# MA18V17.net
KiCad netlist of a schematic drawn in Altium Designer
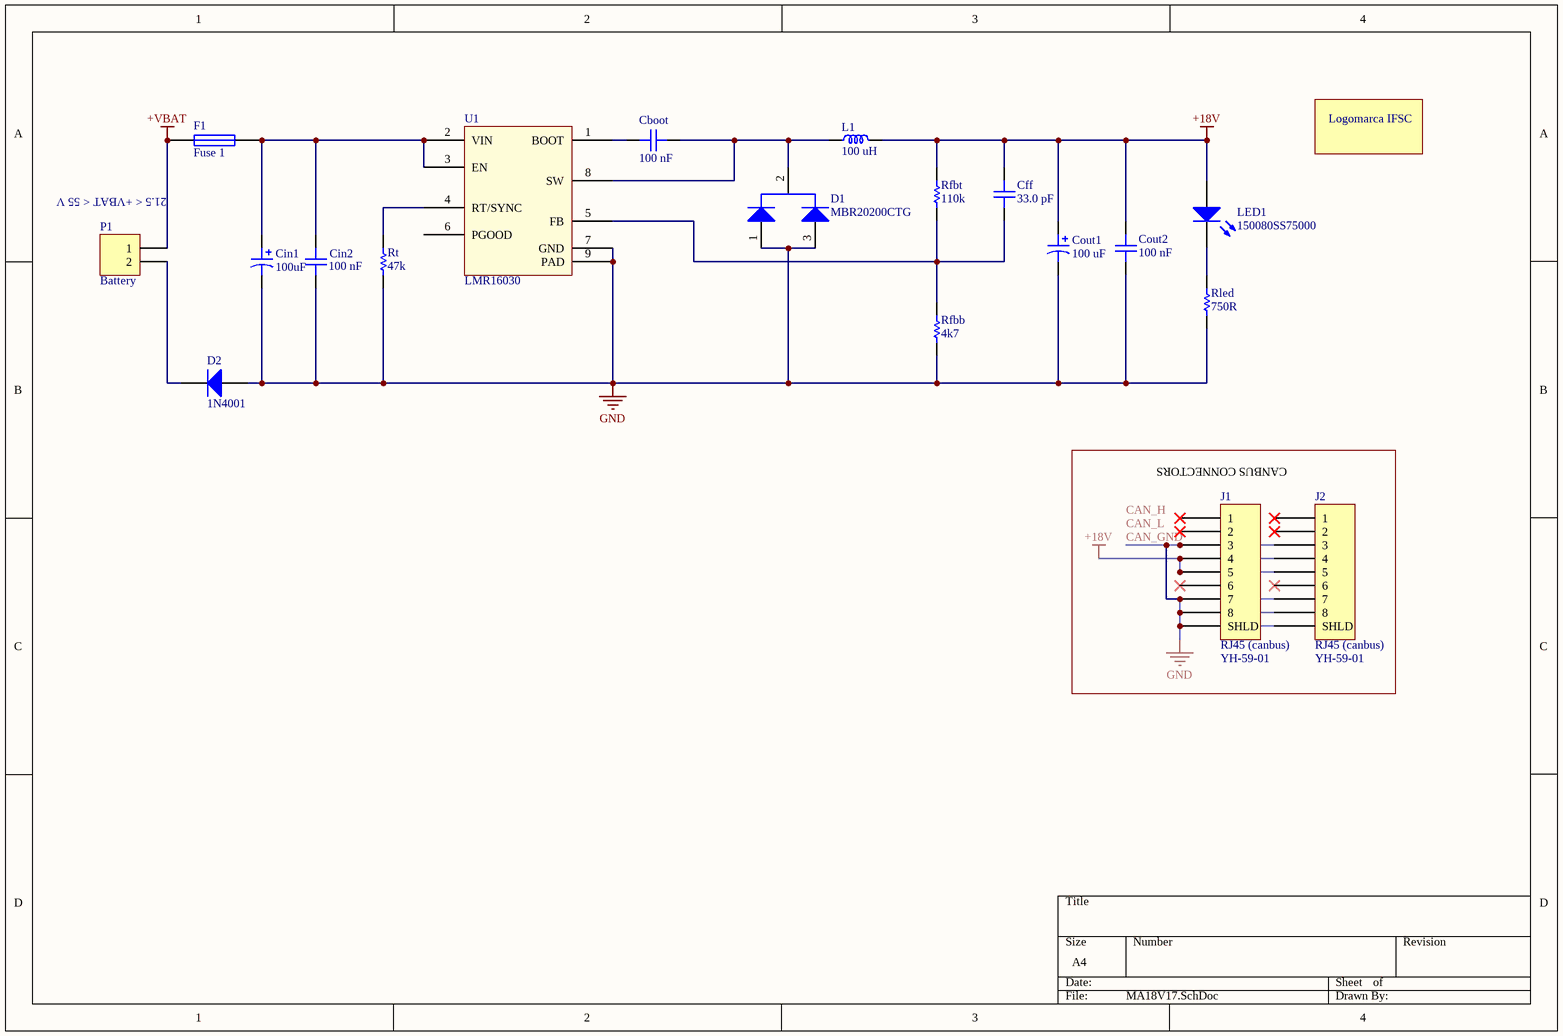
[diagram p0: MA18V17.SchDoc]

(export (version "E")
  (design (tool "Eeschema 10.0.6"))
  (components
    (comp (ref "Cboot")
      (value "100 nF")
      (footprint "0805C")
      (description "Capacitor")
      (fields (field (name "VOLTAGE") "25 V") (field (name "PUBLISHER") "Altium Limited"))
      (libsource (lib "passive") (part "Capacitor"))
    )
    (comp (ref "Cff")
      (value "33.0 pF")
      (footprint "0805C")
      (description "Capacitor")
      (fields (field (name "VOLTAGE") "16 V") (field (name "PUBLISHER") "Altium Limited"))
      (libsource (lib "passive") (part "Capacitor"))
    )
    (comp (ref "Cin1")
      (value "100uF")
      (footprint "CP-RAD-12.5mm-35.0mm-5.0mm")
      (description "Solid Aluminum Capacitor with Organic Semiconductor Electrolyte: 100uF, 10V, Bulk Pack")
      (fields (field (name "VOLTAGE") "100V") (field (name "PUBLISHER") "Altium Limited"))
      (libsource (lib "passive") (part "CapacitorPol"))
    )
    (comp (ref "Cin2")
      (value "100 nF")
      (footprint "0805C")
      (description "Capacitor")
      (fields (field (name "VOLTAGE") "100 V") (field (name "PUBLISHER") "Altium Limited"))
      (libsource (lib "passive") (part "Capacitor"))
    )
    (comp (ref "Cout1")
      (value "100 uF")
      (footprint "CP-RAD-12.5mm-35.0mm-5.0mm")
      (description "Solid Aluminum Capacitor with Organic Semiconductor Electrolyte: 100uF, 10V, Bulk Pack")
      (fields (field (name "VOLTAGE") "25 V") (field (name "PUBLISHER") "Altium Limited"))
      (libsource (lib "passive") (part "CapacitorPol"))
    )
    (comp (ref "Cout2")
      (value "100 nF")
      (footprint "0805C")
      (description "Capacitor")
      (fields (field (name "VOLTAGE") "25 V") (field (name "PUBLISHER") "Altium Limited"))
      (libsource (lib "passive") (part "Capacitor"))
    )
    (comp (ref "D1")
      (value "MBR20200CTG")
      (footprint "TO-220-deitado")
      (description "SWITCHMODE(TM) Power Rectifier, Dual Schottky Rectifiers, 3-Pin TO-220, Pb-Free, Tube")
      (fields (field (name "MANUFACTURER") "On Semiconductor"))
      (libsource (lib "Altium Content Vault") (part "ONSC-D-A1K2A3-3_B"))
    )
    (comp (ref "D2")
      (value "1N4001")
      (footprint "DIO10.46-5.3x2.8")
      (description "1 Amp General Purpose Rectifier")
      (fields (field (name "PUBLISHER") "Altium Limited"))
      (libsource (lib "Miscellaneous Devices") (part "Diode 1N4001"))
    )
    (comp (ref "F1")
      (value "Fuse 1")
      (footprint "5x20")
      (description "Fuse")
      (fields (field (name "PUBLISHER") "Altium Limited"))
      (libsource (lib "Miscellaneous Devices") (part "Fuse 1"))
    )
    (comp (ref "J1")
      (value "RJ45 (canbus)")
      (footprint "ASSMANN A-2004-2-4-LP/FS")
      (description "YH-59-01")
      (fields (field (name "ALTIUM_VALUE") "YH-59-01"))
      (libsource (lib "Connectors") (part "Modular Jack with Shield"))
    )
    (comp (ref "J2")
      (value "RJ45 (canbus)")
      (footprint "ASSMANN A-2004-2-4-LP/FS")
      (description "YH-59-01")
      (fields (field (name "ALTIUM_VALUE") "YH-59-01"))
      (libsource (lib "Connectors") (part "Modular Jack with Shield"))
    )
    (comp (ref "L1")
      (value "100 uH")
      (footprint "Toroldal D:20, H:10")
      (description "Inductor")
      (libsource (lib "passive") (part "Inductor"))
    )
    (comp (ref "LED1")
      (value "150080SS75000")
      (footprint "0805R")
      (description "SMD mono-color Chip LED, WL-SMCW, Super Red")
      (fields (field (name "MANUFACTURER") "Wuerth Elektronik"))
      (libsource (lib "Altium Content Vault") (part "WE-LED_K1A2-2"))
    )
    (comp (ref "P1")
      (value "Battery")
      (footprint "KRE_2")
      (description "Terminal Block 1x2")
      (libsource (lib "connector") (part "KRE_2"))
    )
    (comp (ref "Rfbb")
      (value "4k7")
      (footprint "0805R")
      (description "Resistor")
      (fields
        (field (name "POWER") "1/8 W")
        (field (name "TOLERANCE") "5%")
        (field (name "PUBLISHER") "Altium Limited")
      )
      (libsource (lib "passive") (part "Resistor"))
    )
    (comp (ref "Rfbt")
      (value "110k")
      (footprint "0805R")
      (description "Resistor")
      (fields
        (field (name "POWER") "1/8 W")
        (field (name "TOLERANCE") "5%")
        (field (name "PUBLISHER") "Altium Limited")
      )
      (libsource (lib "passive") (part "Resistor"))
    )
    (comp (ref "Rled")
      (value "750R")
      (footprint "0805R")
      (description "Resistor")
      (fields
        (field (name "POWER") "1/8 W")
        (field (name "TOLERANCE") "5%")
        (field (name "PUBLISHER") "Altium Limited")
      )
      (libsource (lib "passive") (part "Resistor"))
    )
    (comp (ref "Rt")
      (value "47k")
      (footprint "0805R")
      (description "Resistor")
      (fields
        (field (name "POWER") "1/8 W")
        (field (name "TOLERANCE") "5%")
        (field (name "PUBLISHER") "Altium Limited")
      )
      (libsource (lib "passive") (part "Resistor"))
    )
    (comp (ref "U1")
      (value "LMR16030")
      (footprint "lmr16030")
      (libsource (lib "LMR16030") (part "Component_1"))
    )
    (comp (ref "X1")
      (value "Logomarca IFSC")
      (footprint "IFSC_SILK")
      (libsource (lib "R2R - Nova") (part "logomarcaIFSC"))
    )
  )
  (nets
    (net (code "1") (name "+18V") (class "Default")
      (node (ref "Cff") (pin "2") (pinfunction "2_2") (pintype "passive"))
      (node (ref "Cout1") (pin "1") (pinfunction "1_1") (pintype "passive"))
      (node (ref "Cout2") (pin "1") (pinfunction "1_1") (pintype "passive"))
      (node (ref "J1") (pin "4") (pinfunction "4_4") (pintype "passive"))
      (node (ref "J1") (pin "5") (pinfunction "5_5") (pintype "passive"))
      (node (ref "J2") (pin "4") (pinfunction "4_4") (pintype "passive"))
      (node (ref "J2") (pin "5") (pinfunction "5_5") (pintype "passive"))
      (node (ref "L1") (pin "2") (pinfunction "2_2") (pintype "passive"))
      (node (ref "LED1") (pin "2") (pinfunction "A_2") (pintype "passive"))
      (node (ref "Rfbt") (pin "2") (pinfunction "2_2") (pintype "passive"))
    )
    (net (code "2") (name "+VBAT") (class "Default")
      (node (ref "F1") (pin "1") (pinfunction "1_1") (pintype "passive"))
      (node (ref "P1") (pin "1") (pinfunction "1_1") (pintype "passive"))
    )
    (net (code "5") (name "GND") (class "Default")
      (node (ref "Cin1") (pin "2") (pinfunction "2_2") (pintype "passive"))
      (node (ref "Cin2") (pin "2") (pinfunction "2_2") (pintype "passive"))
      (node (ref "Cout1") (pin "2") (pinfunction "2_2") (pintype "passive"))
      (node (ref "Cout2") (pin "2") (pinfunction "2_2") (pintype "passive"))
      (node (ref "D1") (pin "1") (pinfunction "A1_1") (pintype "passive"))
      (node (ref "D1") (pin "3") (pinfunction "A2_3") (pintype "passive"))
      (node (ref "D2") (pin "1") (pinfunction "A_1") (pintype "passive"))
      (node (ref "J1") (pin "3") (pinfunction "3_3") (pintype "passive"))
      (node (ref "J1") (pin "7") (pinfunction "7_7") (pintype "passive"))
      (node (ref "J1") (pin "8") (pinfunction "8_8") (pintype "passive"))
      (node (ref "J1") (pin "S") (pinfunction "SHLD_S") (pintype "passive"))
      (node (ref "J2") (pin "3") (pinfunction "3_3") (pintype "passive"))
      (node (ref "J2") (pin "7") (pinfunction "7_7") (pintype "passive"))
      (node (ref "J2") (pin "8") (pinfunction "8_8") (pintype "passive"))
      (node (ref "J2") (pin "S") (pinfunction "SHLD_S") (pintype "passive"))
      (node (ref "Rfbb") (pin "1") (pinfunction "1_1") (pintype "passive"))
      (node (ref "Rled") (pin "1") (pinfunction "1_1") (pintype "passive"))
      (node (ref "Rt") (pin "2") (pinfunction "2_2") (pintype "passive"))
      (node (ref "U1") (pin "7") (pinfunction "GND_7") (pintype "passive"))
      (node (ref "U1") (pin "9") (pinfunction "PAD_9") (pintype "passive"))
    )
    (net (code "6") (name "Net-(D1-K)") (class "Default")
      (node (ref "Cboot") (pin "1") (pinfunction "1_1") (pintype "passive"))
      (node (ref "D1") (pin "2") (pinfunction "K_2") (pintype "passive"))
      (node (ref "L1") (pin "1") (pinfunction "1_1") (pintype "passive"))
      (node (ref "U1") (pin "8") (pinfunction "SW_8") (pintype "passive"))
    )
    (net (code "7") (name "Net-(D2-K)") (class "Default")
      (node (ref "D2") (pin "2") (pinfunction "K_2") (pintype "passive"))
      (node (ref "P1") (pin "2") (pinfunction "2_2") (pintype "passive"))
    )
    (net (code "8") (name "Net-(LED1-K)") (class "Default")
      (node (ref "LED1") (pin "1") (pinfunction "K_1") (pintype "passive"))
      (node (ref "Rled") (pin "2") (pinfunction "2_2") (pintype "passive"))
    )
    (net (code "9") (name "Net-(U1-BOOT)") (class "Default")
      (node (ref "Cboot") (pin "2") (pinfunction "2_2") (pintype "passive"))
      (node (ref "U1") (pin "1") (pinfunction "BOOT_1") (pintype "passive"))
    )
    (net (code "10") (name "Net-(U1-EN)") (class "Default")
      (node (ref "Cin1") (pin "1") (pinfunction "1_1") (pintype "passive"))
      (node (ref "Cin2") (pin "1") (pinfunction "1_1") (pintype "passive"))
      (node (ref "F1") (pin "2") (pinfunction "2_2") (pintype "passive"))
      (node (ref "U1") (pin "2") (pinfunction "VIN_2") (pintype "passive"))
      (node (ref "U1") (pin "3") (pinfunction "EN_3") (pintype "passive"))
    )
    (net (code "11") (name "Net-(U1-FB)") (class "Default")
      (node (ref "Cff") (pin "1") (pinfunction "1_1") (pintype "passive"))
      (node (ref "Rfbb") (pin "2") (pinfunction "2_2") (pintype "passive"))
      (node (ref "Rfbt") (pin "1") (pinfunction "1_1") (pintype "passive"))
      (node (ref "U1") (pin "5") (pinfunction "FB_5") (pintype "passive"))
    )
    (net (code "12") (name "Net-(U1-RT{slash}SYNC)") (class "Default")
      (node (ref "Rt") (pin "1") (pinfunction "1_1") (pintype "passive"))
      (node (ref "U1") (pin "4") (pinfunction "RT/SYNC_4") (pintype "passive"))
    )
    (net (code "13") (name "unconnected-(J1-Pad1)") (class "Default")
      (node (ref "J1") (pin "1") (pinfunction "1_1") (pintype "passive+no_connect"))
    )
    (net (code "14") (name "unconnected-(J1-Pad2)") (class "Default")
      (node (ref "J1") (pin "2") (pinfunction "2_2") (pintype "passive+no_connect"))
    )
    (net (code "15") (name "unconnected-(J1-Pad6)") (class "Default")
      (node (ref "J1") (pin "6") (pinfunction "6_6") (pintype "passive+no_connect"))
    )
    (net (code "16") (name "unconnected-(J2-Pad1)") (class "Default")
      (node (ref "J2") (pin "1") (pinfunction "1_1") (pintype "passive+no_connect"))
    )
    (net (code "17") (name "unconnected-(J2-Pad2)") (class "Default")
      (node (ref "J2") (pin "2") (pinfunction "2_2") (pintype "passive+no_connect"))
    )
    (net (code "18") (name "unconnected-(J2-Pad6)") (class "Default")
      (node (ref "J2") (pin "6") (pinfunction "6_6") (pintype "passive+no_connect"))
    )
    (net (code "19") (name "unconnected-(U1-PGOOD-Pad6)") (class "Default")
      (node (ref "U1") (pin "6") (pinfunction "PGOOD_6") (pintype "passive"))
    )
  )
)
